# IDCI_WifiNode_PWR.net
KiCad netlist of a schematic drawn in Altium Designer
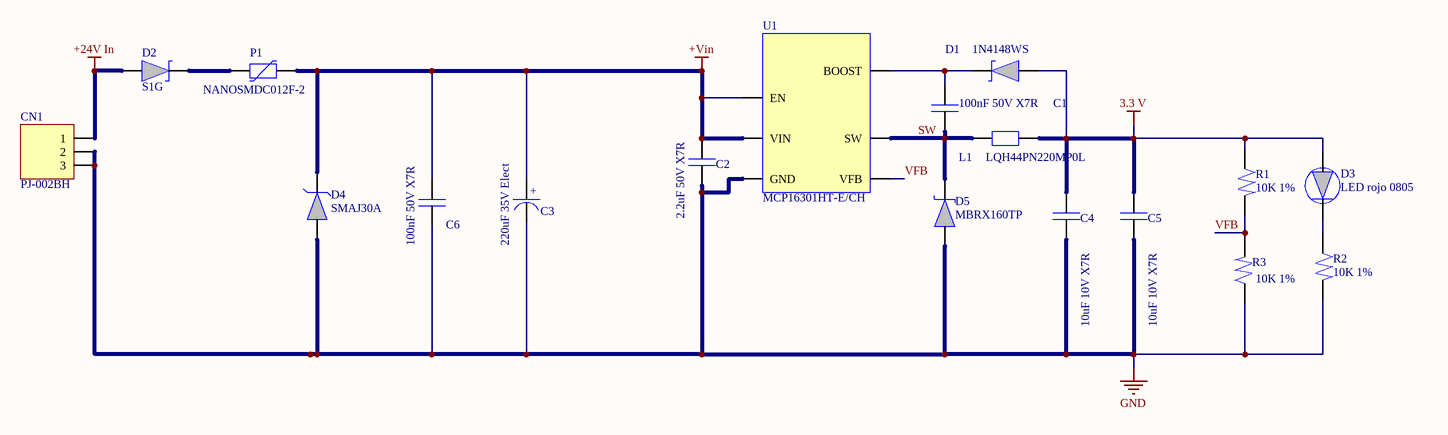
[diagram p0: IDCI_WifiNode_PWR.SchDoc]

(export (version "E")
  (design (tool "Eeschema 10.0.6"))
  (components
    (comp (ref "C1")
      (value "100nF 50V X7R")
      (description "Capacitor AF")
      (libsource (lib "Schlib1") (part "CAPACITOR"))
    )
    (comp (ref "C2")
      (value "2.2uF 50V X7R")
      (description "Capacitor AF")
      (libsource (lib "Schlib1") (part "CAPACITOR"))
    )
    (comp (ref "C3")
      (value "220uF 35V Elect")
      (description "Capacitor polarizado")
      (libsource (lib "Schlib1") (part "POL_CAP"))
    )
    (comp (ref "C4")
      (value "10uF 10V X7R")
      (description "Capacitor AF")
      (libsource (lib "Schlib1") (part "CAPACITOR"))
    )
    (comp (ref "C5")
      (value "10uF 10V X7R")
      (description "Capacitor AF")
      (libsource (lib "Schlib1") (part "CAPACITOR"))
    )
    (comp (ref "C6")
      (value "100nF 50V X7R")
      (description "Capacitor AF")
      (libsource (lib "Schlib1") (part "CAPACITOR"))
    )
    (comp (ref "CN1") (value "PJ-002BH") (libsource (lib "Schlib1") (part "Connector")))
    (comp (ref "D1") (value "1N4148WS") (libsource (lib "Schlib1") (part "TVS_DIODE")))
    (comp (ref "D2") (value "S1G") (libsource (lib "Schlib1") (part "TVS_DIODE")))
    (comp (ref "D3") (value "LED rojo 0805") (libsource (lib "Schlib1") (part "LED_DIODE")))
    (comp (ref "D4") (value "SMAJ30A") (libsource (lib "Schlib1") (part "ZENER_DIODE")))
    (comp (ref "D5") (value "MBRX160TP") (libsource (lib "Schlib1") (part "TVS_DIODE")))
    (comp (ref "L1")
      (value "LQH44PN220MP0L")
      (description "Inductor")
      (libsource (lib "Schlib1") (part "Inductor"))
    )
    (comp (ref "P1")
      (value "NANOSMDC012F-2")
      (description "Polyswitch")
      (libsource (lib "Schlib1") (part "Polyswitch"))
    )
    (comp (ref "R1") (value "10K 1%") (libsource (lib "Schlib1") (part "Resistor")))
    (comp (ref "R2") (value "10K 1%") (libsource (lib "Schlib1") (part "Resistor")))
    (comp (ref "R3") (value "10K 1%") (libsource (lib "Schlib1") (part "Resistor")))
    (comp (ref "U1")
      (value "MCP16301HT-E/CH")
      (description "Driver Switching")
      (libsource (lib "Schlib1") (part "Integrado"))
    )
  )
  (nets
    (net (code "1") (name "+24V In") (class "Default")
      (node (ref "CN1") (pin "42") (pinfunction "1_42") (pintype "passive"))
      (node (ref "D2") (pin "34") (pinfunction "34_34") (pintype "passive"))
    )
    (net (code "2") (name "+Vin") (class "Default")
      (node (ref "C2") (pin "39") (pinfunction "39_39") (pintype "passive"))
      (node (ref "C3") (pin "36") (pinfunction "36_36") (pintype "passive"))
      (node (ref "C6") (pin "39") (pinfunction "39_39") (pintype "passive"))
      (node (ref "D4") (pin "33") (pinfunction "33_33") (pintype "passive"))
      (node (ref "P1") (pin "40") (pinfunction "40_40") (pintype "passive"))
      (node (ref "U1") (pin "49") (pinfunction "EN_49") (pintype "passive"))
      (node (ref "U1") (pin "50") (pinfunction "VIN_50") (pintype "passive"))
    )
    (net (code "3") (name "/SW") (class "Default")
      (node (ref "C1") (pin "38") (pinfunction "38_38") (pintype "passive"))
      (node (ref "D5") (pin "35") (pinfunction "35_35") (pintype "passive"))
      (node (ref "L1") (pin "45") (pinfunction "45_45") (pintype "passive"))
      (node (ref "U1") (pin "52") (pinfunction "SW_52") (pintype "passive"))
    )
    (net (code "4") (name "/VFB") (class "Default")
      (node (ref "R1") (pin "48") (pinfunction "48_48") (pintype "passive"))
      (node (ref "R3") (pin "48") (pinfunction "48_48") (pintype "passive"))
      (node (ref "U1") (pin "54") (pinfunction "VFB_54") (pintype "passive"))
    )
    (net (code "5") (name "3.3 V") (class "Default")
      (node (ref "C4") (pin "39") (pinfunction "39_39") (pintype "passive"))
      (node (ref "C5") (pin "39") (pinfunction "39_39") (pintype "passive"))
      (node (ref "D1") (pin "34") (pinfunction "34_34") (pintype "passive"))
      (node (ref "D3") (pin "31") (pinfunction "31_31") (pintype "passive"))
      (node (ref "L1") (pin "46") (pinfunction "46_46") (pintype "passive"))
      (node (ref "R1") (pin "47") (pinfunction "47_47") (pintype "passive"))
    )
    (net (code "6") (name "GND") (class "Default")
      (node (ref "C2") (pin "38") (pinfunction "38_38") (pintype "passive"))
      (node (ref "C3") (pin "37") (pinfunction "37_37") (pintype "passive"))
      (node (ref "C4") (pin "38") (pinfunction "38_38") (pintype "passive"))
      (node (ref "C5") (pin "38") (pinfunction "38_38") (pintype "passive"))
      (node (ref "C6") (pin "38") (pinfunction "38_38") (pintype "passive"))
      (node (ref "CN1") (pin "43") (pinfunction "2_43") (pintype "passive"))
      (node (ref "CN1") (pin "44") (pinfunction "3_44") (pintype "passive"))
      (node (ref "D4") (pin "32") (pinfunction "32_32") (pintype "passive"))
      (node (ref "D5") (pin "34") (pinfunction "34_34") (pintype "passive"))
      (node (ref "R2") (pin "48") (pinfunction "48_48") (pintype "passive"))
      (node (ref "R3") (pin "47") (pinfunction "47_47") (pintype "passive"))
      (node (ref "U1") (pin "51") (pinfunction "GND_51") (pintype "passive"))
    )
    (net (code "7") (name "Net-(D2-Pad35)") (class "Default")
      (node (ref "D2") (pin "35") (pinfunction "35_35") (pintype "passive"))
      (node (ref "P1") (pin "41") (pinfunction "41_41") (pintype "passive"))
    )
    (net (code "8") (name "Net-(D3-Pad30)") (class "Default")
      (node (ref "D3") (pin "30") (pinfunction "30_30") (pintype "passive"))
      (node (ref "R2") (pin "47") (pinfunction "47_47") (pintype "passive"))
    )
    (net (code "9") (name "Net-(U1-BOOST)") (class "Default")
      (node (ref "C1") (pin "39") (pinfunction "39_39") (pintype "passive"))
      (node (ref "D1") (pin "35") (pinfunction "35_35") (pintype "passive"))
      (node (ref "U1") (pin "53") (pinfunction "BOOST_53") (pintype "passive"))
    )
  )
)
